# SensorController_revB.net
KiCad netlist of a schematic drawn in EAGLE
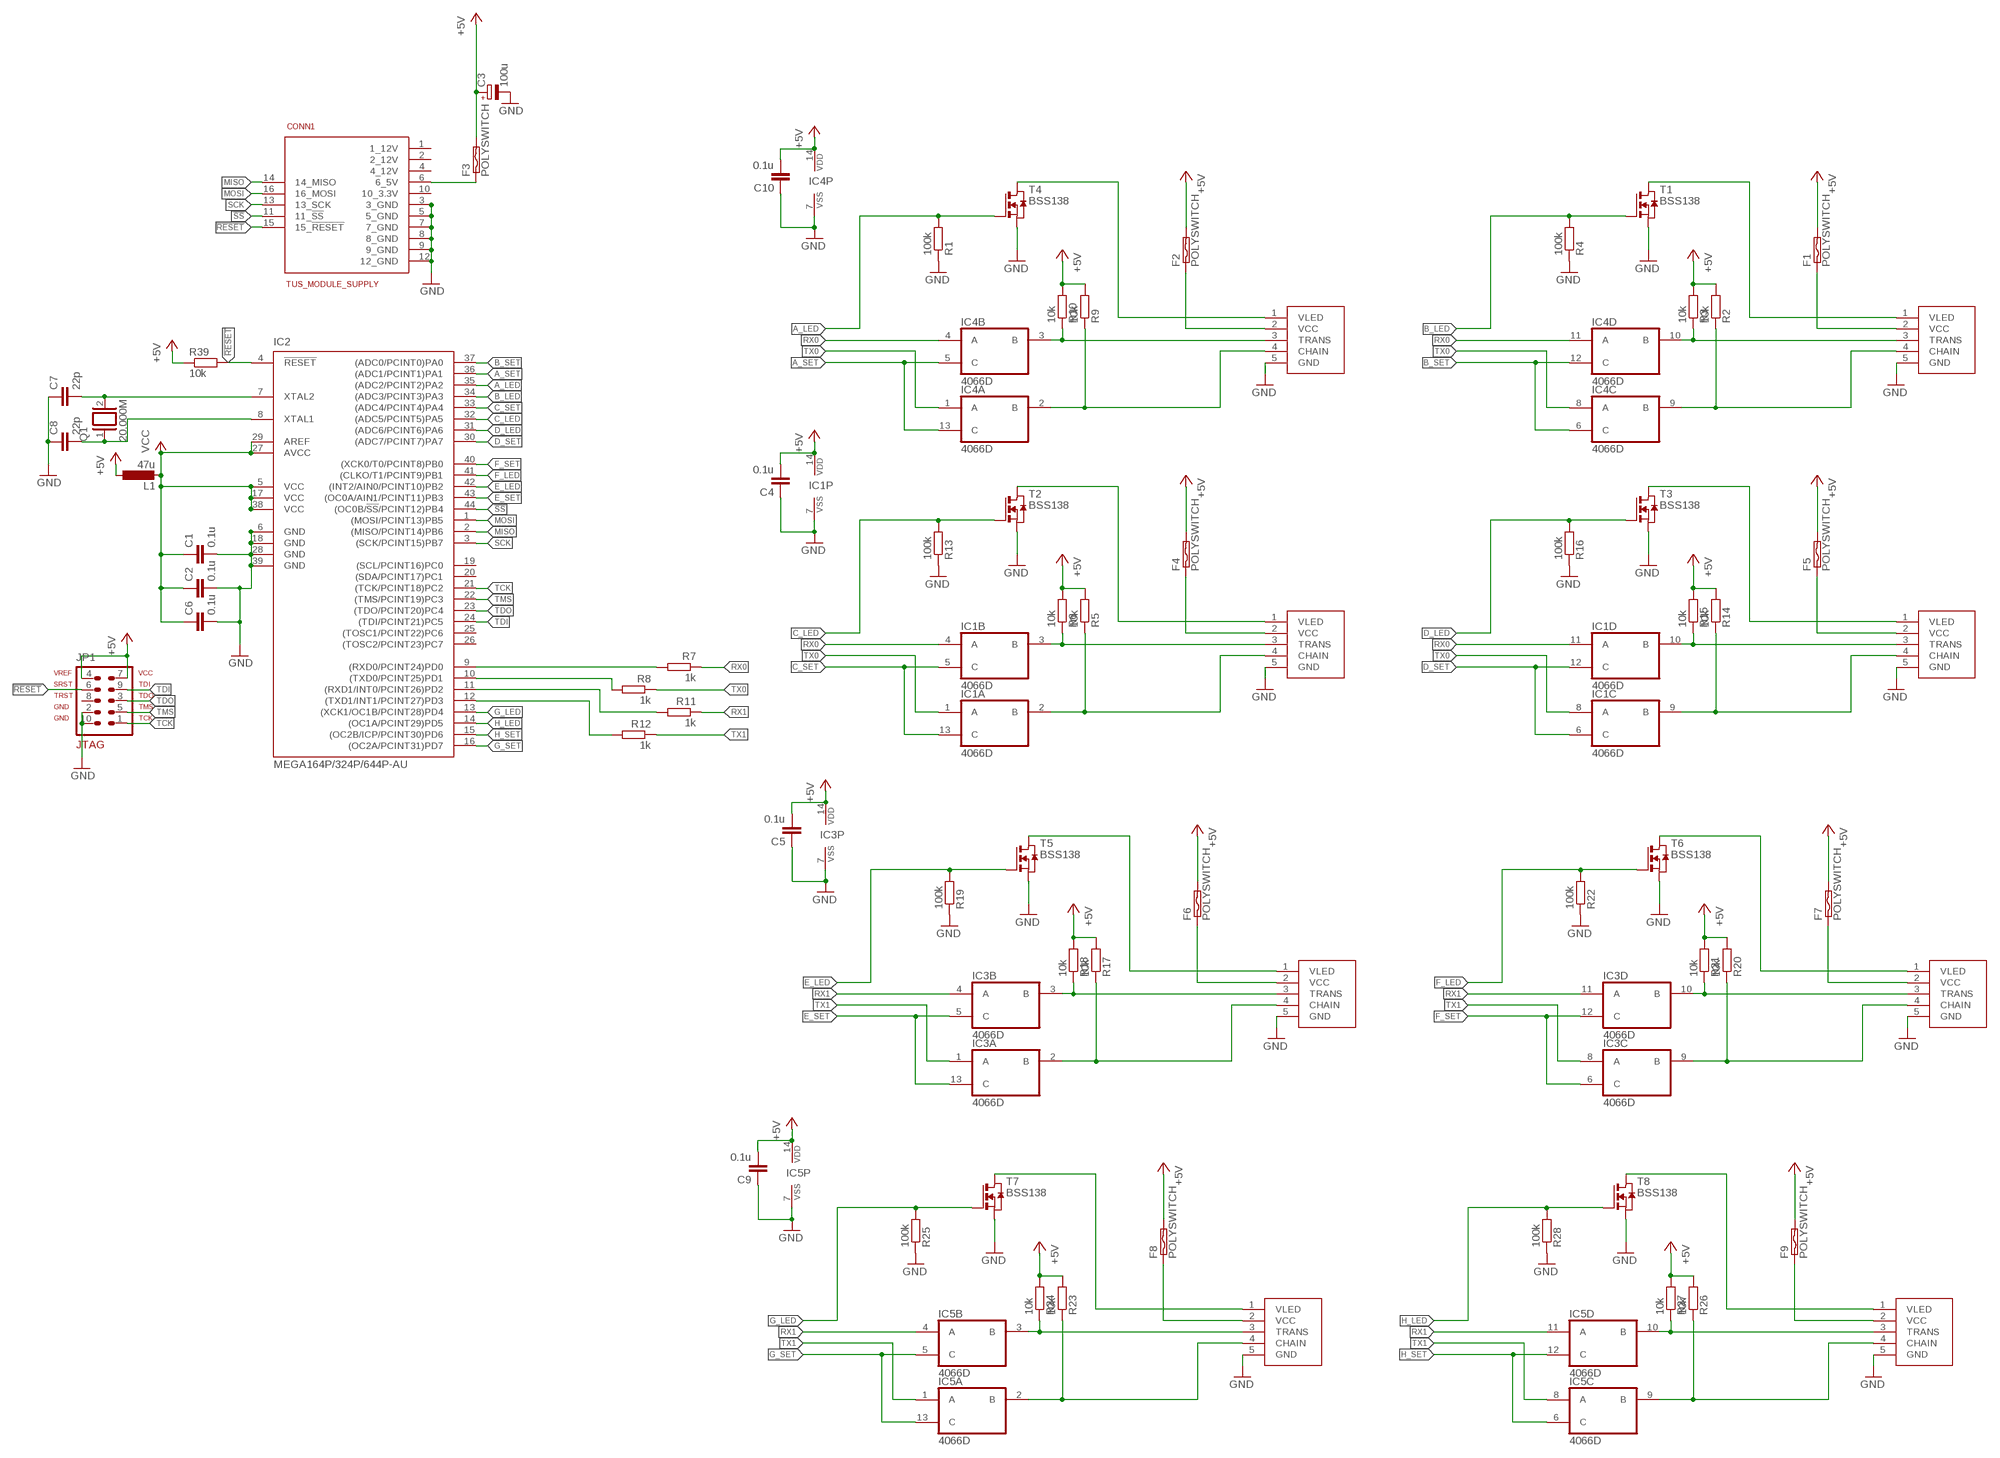
[diagram p0: schematic, sheet 1]

(export (version "E")
  (design (tool "Eeschema 10.0.6"))
  (components
    (comp (ref "A_OUT")
      (value "SERIAL_SENSORXH")
      (footprint "eagle-import:XH-5")
      (libsource (lib "eagle-import") (part "SERIAL_SENSORXH"))
    )
    (comp (ref "B_OUT")
      (value "SERIAL_SENSORXH")
      (footprint "eagle-import:XH-5")
      (libsource (lib "eagle-import") (part "SERIAL_SENSORXH"))
    )
    (comp (ref "C1")
      (value "0.1u")
      (footprint "eagle-import:C1608")
      (libsource (lib "eagle-import") (part "C-EUC1608"))
    )
    (comp (ref "C2")
      (value "0.1u")
      (footprint "eagle-import:C1608")
      (libsource (lib "eagle-import") (part "C-EUC1608"))
    )
    (comp (ref "C3")
      (value "100u")
      (footprint "eagle-import:E2,5-5")
      (libsource (lib "eagle-import") (part "CPOL-EUE2.5-5"))
    )
    (comp (ref "C4")
      (value "0.1u")
      (footprint "eagle-import:C1608")
      (libsource (lib "eagle-import") (part "C-EUC1608"))
    )
    (comp (ref "C5")
      (value "0.1u")
      (footprint "eagle-import:C1608")
      (libsource (lib "eagle-import") (part "C-EUC1608"))
    )
    (comp (ref "C6")
      (value "0.1u")
      (footprint "eagle-import:C1608")
      (libsource (lib "eagle-import") (part "C-EUC1608"))
    )
    (comp (ref "C7")
      (value "22p")
      (footprint "eagle-import:C1608")
      (libsource (lib "eagle-import") (part "C-EUC1608"))
    )
    (comp (ref "C8")
      (value "22p")
      (footprint "eagle-import:C1608")
      (libsource (lib "eagle-import") (part "C-EUC1608"))
    )
    (comp (ref "C9")
      (value "0.1u")
      (footprint "eagle-import:C1608")
      (libsource (lib "eagle-import") (part "C-EUC1608"))
    )
    (comp (ref "C10")
      (value "0.1u")
      (footprint "eagle-import:C1608")
      (libsource (lib "eagle-import") (part "C-EUC1608"))
    )
    (comp (ref "CONN1")
      (value "TUS_MODULE_SUPPLY")
      (footprint "eagle-import:2X08")
      (libsource (lib "eagle-import") (part "TUS_MODULE_SUPPLY"))
    )
    (comp (ref "C_OUT")
      (value "SERIAL_SENSORXH")
      (footprint "eagle-import:XH-5")
      (libsource (lib "eagle-import") (part "SERIAL_SENSORXH"))
    )
    (comp (ref "D_OUT")
      (value "SERIAL_SENSORXH")
      (footprint "eagle-import:XH-5")
      (libsource (lib "eagle-import") (part "SERIAL_SENSORXH"))
    )
    (comp (ref "E_OUT")
      (value "SERIAL_SENSORXH")
      (footprint "eagle-import:XH-5")
      (libsource (lib "eagle-import") (part "SERIAL_SENSORXH"))
    )
    (comp (ref "F1")
      (value "POLYSWITCH")
      (footprint "eagle-import:0207_2V")
      (libsource (lib "eagle-import") (part "POLYSWITCH"))
    )
    (comp (ref "F2")
      (value "POLYSWITCH")
      (footprint "eagle-import:0207_2V")
      (libsource (lib "eagle-import") (part "POLYSWITCH"))
    )
    (comp (ref "F3")
      (value "POLYSWITCH")
      (footprint "eagle-import:0207_2V")
      (libsource (lib "eagle-import") (part "POLYSWITCH"))
    )
    (comp (ref "F4")
      (value "POLYSWITCH")
      (footprint "eagle-import:0207_2V")
      (libsource (lib "eagle-import") (part "POLYSWITCH"))
    )
    (comp (ref "F5")
      (value "POLYSWITCH")
      (footprint "eagle-import:0207_2V")
      (libsource (lib "eagle-import") (part "POLYSWITCH"))
    )
    (comp (ref "F6")
      (value "POLYSWITCH")
      (footprint "eagle-import:0207_2V")
      (libsource (lib "eagle-import") (part "POLYSWITCH"))
    )
    (comp (ref "F7")
      (value "POLYSWITCH")
      (footprint "eagle-import:0207_2V")
      (libsource (lib "eagle-import") (part "POLYSWITCH"))
    )
    (comp (ref "F8")
      (value "POLYSWITCH")
      (footprint "eagle-import:0207_2V")
      (libsource (lib "eagle-import") (part "POLYSWITCH"))
    )
    (comp (ref "F9")
      (value "POLYSWITCH")
      (footprint "eagle-import:0207_2V")
      (libsource (lib "eagle-import") (part "POLYSWITCH"))
    )
    (comp (ref "F_OUT")
      (value "SERIAL_SENSORXH")
      (footprint "eagle-import:XH-5")
      (libsource (lib "eagle-import") (part "SERIAL_SENSORXH"))
    )
    (comp (ref "G_OUT")
      (value "SERIAL_SENSORXH")
      (footprint "eagle-import:XH-5")
      (libsource (lib "eagle-import") (part "SERIAL_SENSORXH"))
    )
    (comp (ref "H_OUT")
      (value "SERIAL_SENSORXH")
      (footprint "eagle-import:XH-5")
      (libsource (lib "eagle-import") (part "SERIAL_SENSORXH"))
    )
    (comp (ref "IC1")
      (value "4066D")
      (footprint "eagle-import:SO14")
      (libsource (lib "eagle-import") (part "4066D"))
    )
    (comp (ref "IC2")
      (value "MEGA164P/324P/644P-AU")
      (footprint "eagle-import:TQFP44")
      (libsource (lib "eagle-import") (part "MEGA164P/324P/644P-AU"))
    )
    (comp (ref "IC3")
      (value "4066D")
      (footprint "eagle-import:SO14")
      (libsource (lib "eagle-import") (part "4066D"))
    )
    (comp (ref "IC4")
      (value "4066D")
      (footprint "eagle-import:SO14")
      (libsource (lib "eagle-import") (part "4066D"))
    )
    (comp (ref "IC5")
      (value "4066D")
      (footprint "eagle-import:SO14")
      (libsource (lib "eagle-import") (part "4066D"))
    )
    (comp (ref "JP1")
      (value "AVR-JTAG-10")
      (footprint "eagle-import:AVR-JTAG-10")
      (libsource (lib "eagle-import") (part "AVR-JTAG-10"))
    )
    (comp (ref "L1")
      (value "47u")
      (footprint "eagle-import:L1812")
      (libsource (lib "eagle-import") (part "L-EUL1812"))
    )
    (comp (ref "Q1")
      (value "20.000M")
      (footprint "eagle-import:QS")
      (libsource (lib "eagle-import") (part "XTAL/S"))
    )
    (comp (ref "R1")
      (value "100k")
      (footprint "eagle-import:R0603")
      (libsource (lib "eagle-import") (part "R-EU_R0603"))
    )
    (comp (ref "R2")
      (value "10k")
      (footprint "eagle-import:R0603")
      (libsource (lib "eagle-import") (part "R-EU_R0603"))
    )
    (comp (ref "R3")
      (value "10k")
      (footprint "eagle-import:R0603")
      (libsource (lib "eagle-import") (part "R-EU_R0603"))
    )
    (comp (ref "R4")
      (value "100k")
      (footprint "eagle-import:R0603")
      (libsource (lib "eagle-import") (part "R-EU_R0603"))
    )
    (comp (ref "R5")
      (value "10k")
      (footprint "eagle-import:R0603")
      (libsource (lib "eagle-import") (part "R-EU_R0603"))
    )
    (comp (ref "R6")
      (value "10k")
      (footprint "eagle-import:R0603")
      (libsource (lib "eagle-import") (part "R-EU_R0603"))
    )
    (comp (ref "R7")
      (value "1k")
      (footprint "eagle-import:R0603")
      (libsource (lib "eagle-import") (part "R-EU_R0603"))
    )
    (comp (ref "R8")
      (value "1k")
      (footprint "eagle-import:R0603")
      (libsource (lib "eagle-import") (part "R-EU_R0603"))
    )
    (comp (ref "R9")
      (value "10k")
      (footprint "eagle-import:R0603")
      (libsource (lib "eagle-import") (part "R-EU_R0603"))
    )
    (comp (ref "R10")
      (value "10k")
      (footprint "eagle-import:R0603")
      (libsource (lib "eagle-import") (part "R-EU_R0603"))
    )
    (comp (ref "R11")
      (value "1k")
      (footprint "eagle-import:R0603")
      (libsource (lib "eagle-import") (part "R-EU_R0603"))
    )
    (comp (ref "R12")
      (value "1k")
      (footprint "eagle-import:R0603")
      (libsource (lib "eagle-import") (part "R-EU_R0603"))
    )
    (comp (ref "R13")
      (value "100k")
      (footprint "eagle-import:R0603")
      (libsource (lib "eagle-import") (part "R-EU_R0603"))
    )
    (comp (ref "R14")
      (value "10k")
      (footprint "eagle-import:R0603")
      (libsource (lib "eagle-import") (part "R-EU_R0603"))
    )
    (comp (ref "R15")
      (value "10k")
      (footprint "eagle-import:R0603")
      (libsource (lib "eagle-import") (part "R-EU_R0603"))
    )
    (comp (ref "R16")
      (value "100k")
      (footprint "eagle-import:R0603")
      (libsource (lib "eagle-import") (part "R-EU_R0603"))
    )
    (comp (ref "R17")
      (value "10k")
      (footprint "eagle-import:R0603")
      (libsource (lib "eagle-import") (part "R-EU_R0603"))
    )
    (comp (ref "R18")
      (value "10k")
      (footprint "eagle-import:R0603")
      (libsource (lib "eagle-import") (part "R-EU_R0603"))
    )
    (comp (ref "R19")
      (value "100k")
      (footprint "eagle-import:R0603")
      (libsource (lib "eagle-import") (part "R-EU_R0603"))
    )
    (comp (ref "R20")
      (value "10k")
      (footprint "eagle-import:R0603")
      (libsource (lib "eagle-import") (part "R-EU_R0603"))
    )
    (comp (ref "R21")
      (value "10k")
      (footprint "eagle-import:R0603")
      (libsource (lib "eagle-import") (part "R-EU_R0603"))
    )
    (comp (ref "R22")
      (value "100k")
      (footprint "eagle-import:R0603")
      (libsource (lib "eagle-import") (part "R-EU_R0603"))
    )
    (comp (ref "R23")
      (value "10k")
      (footprint "eagle-import:R0603")
      (libsource (lib "eagle-import") (part "R-EU_R0603"))
    )
    (comp (ref "R24")
      (value "10k")
      (footprint "eagle-import:R0603")
      (libsource (lib "eagle-import") (part "R-EU_R0603"))
    )
    (comp (ref "R25")
      (value "100k")
      (footprint "eagle-import:R0603")
      (libsource (lib "eagle-import") (part "R-EU_R0603"))
    )
    (comp (ref "R26")
      (value "10k")
      (footprint "eagle-import:R0603")
      (libsource (lib "eagle-import") (part "R-EU_R0603"))
    )
    (comp (ref "R27")
      (value "10k")
      (footprint "eagle-import:R0603")
      (libsource (lib "eagle-import") (part "R-EU_R0603"))
    )
    (comp (ref "R28")
      (value "100k")
      (footprint "eagle-import:R0603")
      (libsource (lib "eagle-import") (part "R-EU_R0603"))
    )
    (comp (ref "R39")
      (value "10k")
      (footprint "eagle-import:R0603")
      (libsource (lib "eagle-import") (part "R-EU_R0603"))
    )
    (comp (ref "T1")
      (value "BSS138")
      (footprint "eagle-import:SOT-23")
      (libsource (lib "eagle-import") (part "NMOSSOT23"))
    )
    (comp (ref "T2")
      (value "BSS138")
      (footprint "eagle-import:SOT-23")
      (libsource (lib "eagle-import") (part "NMOSSOT23"))
    )
    (comp (ref "T3")
      (value "BSS138")
      (footprint "eagle-import:SOT-23")
      (libsource (lib "eagle-import") (part "NMOSSOT23"))
    )
    (comp (ref "T4")
      (value "BSS138")
      (footprint "eagle-import:SOT-23")
      (libsource (lib "eagle-import") (part "NMOSSOT23"))
    )
    (comp (ref "T5")
      (value "BSS138")
      (footprint "eagle-import:SOT-23")
      (libsource (lib "eagle-import") (part "NMOSSOT23"))
    )
    (comp (ref "T6")
      (value "BSS138")
      (footprint "eagle-import:SOT-23")
      (libsource (lib "eagle-import") (part "NMOSSOT23"))
    )
    (comp (ref "T7")
      (value "BSS138")
      (footprint "eagle-import:SOT-23")
      (libsource (lib "eagle-import") (part "NMOSSOT23"))
    )
    (comp (ref "T8")
      (value "BSS138")
      (footprint "eagle-import:SOT-23")
      (libsource (lib "eagle-import") (part "NMOSSOT23"))
    )
  )
  (nets
    (net (code "1") (name "+5V") (class "Default")
      (node (ref "C10") (pin "2") (pinfunction "2_2") (pintype "passive"))
      (node (ref "C3") (pin "+") (pinfunction "+_+") (pintype "passive"))
      (node (ref "C4") (pin "2") (pinfunction "2_2") (pintype "passive"))
      (node (ref "C5") (pin "2") (pinfunction "2_2") (pintype "passive"))
      (node (ref "C9") (pin "2") (pinfunction "2_2") (pintype "passive"))
      (node (ref "F1") (pin "2") (pinfunction "2_2") (pintype "passive"))
      (node (ref "F2") (pin "2") (pinfunction "2_2") (pintype "passive"))
      (node (ref "F3") (pin "2") (pinfunction "2_2") (pintype "passive"))
      (node (ref "F4") (pin "2") (pinfunction "2_2") (pintype "passive"))
      (node (ref "F5") (pin "2") (pinfunction "2_2") (pintype "passive"))
      (node (ref "F6") (pin "2") (pinfunction "2_2") (pintype "passive"))
      (node (ref "F7") (pin "2") (pinfunction "2_2") (pintype "passive"))
      (node (ref "F8") (pin "2") (pinfunction "2_2") (pintype "passive"))
      (node (ref "F9") (pin "2") (pinfunction "2_2") (pintype "passive"))
      (node (ref "IC1") (pin "14") (pinfunction "VDD_14") (pintype "power_in"))
      (node (ref "IC3") (pin "14") (pinfunction "VDD_14") (pintype "power_in"))
      (node (ref "IC4") (pin "14") (pinfunction "VDD_14") (pintype "power_in"))
      (node (ref "IC5") (pin "14") (pinfunction "VDD_14") (pintype "power_in"))
      (node (ref "JP1") (pin "4") (pinfunction "4_4") (pintype "passive"))
      (node (ref "JP1") (pin "7") (pinfunction "7_7") (pintype "passive"))
      (node (ref "L1") (pin "1") (pinfunction "1_1") (pintype "passive"))
      (node (ref "R10") (pin "2") (pinfunction "2_2") (pintype "passive"))
      (node (ref "R14") (pin "2") (pinfunction "2_2") (pintype "passive"))
      (node (ref "R15") (pin "2") (pinfunction "2_2") (pintype "passive"))
      (node (ref "R17") (pin "2") (pinfunction "2_2") (pintype "passive"))
      (node (ref "R18") (pin "2") (pinfunction "2_2") (pintype "passive"))
      (node (ref "R2") (pin "2") (pinfunction "2_2") (pintype "passive"))
      (node (ref "R20") (pin "2") (pinfunction "2_2") (pintype "passive"))
      (node (ref "R21") (pin "2") (pinfunction "2_2") (pintype "passive"))
      (node (ref "R23") (pin "2") (pinfunction "2_2") (pintype "passive"))
      (node (ref "R24") (pin "2") (pinfunction "2_2") (pintype "passive"))
      (node (ref "R26") (pin "2") (pinfunction "2_2") (pintype "passive"))
      (node (ref "R27") (pin "2") (pinfunction "2_2") (pintype "passive"))
      (node (ref "R3") (pin "2") (pinfunction "2_2") (pintype "passive"))
      (node (ref "R39") (pin "1") (pinfunction "1_1") (pintype "passive"))
      (node (ref "R5") (pin "2") (pinfunction "2_2") (pintype "passive"))
      (node (ref "R6") (pin "2") (pinfunction "2_2") (pintype "passive"))
      (node (ref "R9") (pin "2") (pinfunction "2_2") (pintype "passive"))
    )
    (net (code "2") (name "/~{RESET}") (class "Default")
      (node (ref "CONN1") (pin "15") (pinfunction "15_~{RESET}_15") (pintype "bidirectional"))
      (node (ref "IC2") (pin "4") (pinfunction "~{RESET}_4") (pintype "input"))
      (node (ref "JP1") (pin "6") (pinfunction "6_6") (pintype "passive"))
      (node (ref "R39") (pin "2") (pinfunction "2_2") (pintype "passive"))
    )
    (net (code "3") (name "/~{SS}") (class "Default")
      (node (ref "CONN1") (pin "11") (pinfunction "11_~{SS}_11") (pintype "bidirectional"))
      (node (ref "IC2") (pin "44") (pinfunction "(OC0B/~{SS}/PCINT12)PB4_44") (pintype "bidirectional"))
    )
    (net (code "4") (name "A_LED") (class "Default")
      (node (ref "IC2") (pin "35") (pinfunction "(ADC2/PCINT2)PA2_35") (pintype "bidirectional"))
      (node (ref "R1") (pin "2") (pinfunction "2_2") (pintype "passive"))
      (node (ref "T4") (pin "3") (pinfunction "G_3") (pintype "passive"))
    )
    (net (code "5") (name "A_SET") (class "Default")
      (node (ref "IC2") (pin "36") (pinfunction "(ADC1/PCINT1)PA1_36") (pintype "bidirectional"))
      (node (ref "IC4") (pin "13") (pinfunction "C_13") (pintype "input"))
      (node (ref "IC4") (pin "5") (pinfunction "C_5") (pintype "input"))
    )
    (net (code "6") (name "B_LED") (class "Default")
      (node (ref "IC2") (pin "34") (pinfunction "(ADC3/PCINT3)PA3_34") (pintype "bidirectional"))
      (node (ref "R4") (pin "2") (pinfunction "2_2") (pintype "passive"))
      (node (ref "T1") (pin "3") (pinfunction "G_3") (pintype "passive"))
    )
    (net (code "7") (name "B_SET") (class "Default")
      (node (ref "IC2") (pin "37") (pinfunction "(ADC0/PCINT0)PA0_37") (pintype "bidirectional"))
      (node (ref "IC4") (pin "12") (pinfunction "C_12") (pintype "input"))
      (node (ref "IC4") (pin "6") (pinfunction "C_6") (pintype "input"))
    )
    (net (code "8") (name "C_LED") (class "Default")
      (node (ref "IC2") (pin "32") (pinfunction "(ADC5/PCINT5)PA5_32") (pintype "bidirectional"))
      (node (ref "R13") (pin "2") (pinfunction "2_2") (pintype "passive"))
      (node (ref "T2") (pin "3") (pinfunction "G_3") (pintype "passive"))
    )
    (net (code "9") (name "C_SET") (class "Default")
      (node (ref "IC1") (pin "13") (pinfunction "C_13") (pintype "input"))
      (node (ref "IC1") (pin "5") (pinfunction "C_5") (pintype "input"))
      (node (ref "IC2") (pin "33") (pinfunction "(ADC4/PCINT4)PA4_33") (pintype "bidirectional"))
    )
    (net (code "10") (name "D_LED") (class "Default")
      (node (ref "IC2") (pin "31") (pinfunction "(ADC6/PCINT6)PA6_31") (pintype "bidirectional"))
      (node (ref "R16") (pin "2") (pinfunction "2_2") (pintype "passive"))
      (node (ref "T3") (pin "3") (pinfunction "G_3") (pintype "passive"))
    )
    (net (code "11") (name "D_SET") (class "Default")
      (node (ref "IC1") (pin "12") (pinfunction "C_12") (pintype "input"))
      (node (ref "IC1") (pin "6") (pinfunction "C_6") (pintype "input"))
      (node (ref "IC2") (pin "30") (pinfunction "(ADC7/PCINT7)PA7_30") (pintype "bidirectional"))
    )
    (net (code "12") (name "E_LED") (class "Default")
      (node (ref "IC2") (pin "42") (pinfunction "(INT2/AIN0/PCINT10)PB2_42") (pintype "bidirectional"))
      (node (ref "R19") (pin "2") (pinfunction "2_2") (pintype "passive"))
      (node (ref "T5") (pin "3") (pinfunction "G_3") (pintype "passive"))
    )
    (net (code "13") (name "E_SET") (class "Default")
      (node (ref "IC2") (pin "43") (pinfunction "(OC0A/AIN1/PCINT11)PB3_43") (pintype "bidirectional"))
      (node (ref "IC3") (pin "13") (pinfunction "C_13") (pintype "input"))
      (node (ref "IC3") (pin "5") (pinfunction "C_5") (pintype "input"))
    )
    (net (code "14") (name "F_LED") (class "Default")
      (node (ref "IC2") (pin "41") (pinfunction "(CLKO/T1/PCINT9)PB1_41") (pintype "bidirectional"))
      (node (ref "R22") (pin "2") (pinfunction "2_2") (pintype "passive"))
      (node (ref "T6") (pin "3") (pinfunction "G_3") (pintype "passive"))
    )
    (net (code "15") (name "F_SET") (class "Default")
      (node (ref "IC2") (pin "40") (pinfunction "(XCK0/T0/PCINT8)PB0_40") (pintype "bidirectional"))
      (node (ref "IC3") (pin "12") (pinfunction "C_12") (pintype "input"))
      (node (ref "IC3") (pin "6") (pinfunction "C_6") (pintype "input"))
    )
    (net (code "16") (name "GND") (class "Default")
      (node (ref "A_OUT") (pin "5") (pinfunction "GND_5") (pintype "bidirectional"))
      (node (ref "B_OUT") (pin "5") (pinfunction "GND_5") (pintype "bidirectional"))
      (node (ref "C1") (pin "2") (pinfunction "2_2") (pintype "passive"))
      (node (ref "C10") (pin "1") (pinfunction "1_1") (pintype "passive"))
      (node (ref "C2") (pin "2") (pinfunction "2_2") (pintype "passive"))
      (node (ref "C3") (pin "-") (pinfunction "-_-") (pintype "passive"))
      (node (ref "C4") (pin "1") (pinfunction "1_1") (pintype "passive"))
      (node (ref "C5") (pin "1") (pinfunction "1_1") (pintype "passive"))
      (node (ref "C6") (pin "2") (pinfunction "2_2") (pintype "passive"))
      (node (ref "C7") (pin "1") (pinfunction "1_1") (pintype "passive"))
      (node (ref "C8") (pin "1") (pinfunction "1_1") (pintype "passive"))
      (node (ref "C9") (pin "1") (pinfunction "1_1") (pintype "passive"))
      (node (ref "CONN1") (pin "12") (pinfunction "12_GND_12") (pintype "bidirectional"))
      (node (ref "CONN1") (pin "3") (pinfunction "3_GND_3") (pintype "bidirectional"))
      (node (ref "CONN1") (pin "5") (pinfunction "5_GND_5") (pintype "bidirectional"))
      (node (ref "CONN1") (pin "7") (pinfunction "7_GND_7") (pintype "bidirectional"))
      (node (ref "CONN1") (pin "8") (pinfunction "8_GND_8") (pintype "bidirectional"))
      (node (ref "CONN1") (pin "9") (pinfunction "9_GND_9") (pintype "bidirectional"))
      (node (ref "C_OUT") (pin "5") (pinfunction "GND_5") (pintype "bidirectional"))
      (node (ref "D_OUT") (pin "5") (pinfunction "GND_5") (pintype "bidirectional"))
      (node (ref "E_OUT") (pin "5") (pinfunction "GND_5") (pintype "bidirectional"))
      (node (ref "F_OUT") (pin "5") (pinfunction "GND_5") (pintype "bidirectional"))
      (node (ref "G_OUT") (pin "5") (pinfunction "GND_5") (pintype "bidirectional"))
      (node (ref "H_OUT") (pin "5") (pinfunction "GND_5") (pintype "bidirectional"))
      (node (ref "IC1") (pin "7") (pinfunction "VSS_7") (pintype "power_in"))
      (node (ref "IC2") (pin "18") (pinfunction "GND_18") (pintype "power_in"))
      (node (ref "IC2") (pin "28") (pinfunction "GND_28") (pintype "power_in"))
      (node (ref "IC2") (pin "39") (pinfunction "GND_39") (pintype "power_in"))
      (node (ref "IC2") (pin "6") (pinfunction "GND_6") (pintype "power_in"))
      (node (ref "IC3") (pin "7") (pinfunction "VSS_7") (pintype "power_in"))
      (node (ref "IC4") (pin "7") (pinfunction "VSS_7") (pintype "power_in"))
      (node (ref "IC5") (pin "7") (pinfunction "VSS_7") (pintype "power_in"))
      (node (ref "JP1") (pin "10") (pinfunction "10_10") (pintype "passive"))
      (node (ref "JP1") (pin "2") (pinfunction "2_2") (pintype "passive"))
      (node (ref "R1") (pin "1") (pinfunction "1_1") (pintype "passive"))
      (node (ref "R13") (pin "1") (pinfunction "1_1") (pintype "passive"))
      (node (ref "R16") (pin "1") (pinfunction "1_1") (pintype "passive"))
      (node (ref "R19") (pin "1") (pinfunction "1_1") (pintype "passive"))
      (node (ref "R22") (pin "1") (pinfunction "1_1") (pintype "passive"))
      (node (ref "R25") (pin "1") (pinfunction "1_1") (pintype "passive"))
      (node (ref "R28") (pin "1") (pinfunction "1_1") (pintype "passive"))
      (node (ref "R4") (pin "1") (pinfunction "1_1") (pintype "passive"))
      (node (ref "T1") (pin "2") (pinfunction "S_2") (pintype "passive"))
      (node (ref "T2") (pin "2") (pinfunction "S_2") (pintype "passive"))
      (node (ref "T3") (pin "2") (pinfunction "S_2") (pintype "passive"))
      (node (ref "T4") (pin "2") (pinfunction "S_2") (pintype "passive"))
      (node (ref "T5") (pin "2") (pinfunction "S_2") (pintype "passive"))
      (node (ref "T6") (pin "2") (pinfunction "S_2") (pintype "passive"))
      (node (ref "T7") (pin "2") (pinfunction "S_2") (pintype "passive"))
      (node (ref "T8") (pin "2") (pinfunction "S_2") (pintype "passive"))
    )
    (net (code "17") (name "G_LED") (class "Default")
      (node (ref "IC2") (pin "13") (pinfunction "(XCK1/OC1B/PCINT28)PD4_13") (pintype "bidirectional"))
      (node (ref "R25") (pin "2") (pinfunction "2_2") (pintype "passive"))
      (node (ref "T7") (pin "3") (pinfunction "G_3") (pintype "passive"))
    )
    (net (code "18") (name "G_SET") (class "Default")
      (node (ref "IC2") (pin "16") (pinfunction "(OC2A/PCINT31)PD7_16") (pintype "bidirectional"))
      (node (ref "IC5") (pin "13") (pinfunction "C_13") (pintype "input"))
      (node (ref "IC5") (pin "5") (pinfunction "C_5") (pintype "input"))
    )
    (net (code "19") (name "H_LED") (class "Default")
      (node (ref "IC2") (pin "14") (pinfunction "(OC1A/PCINT29)PD5_14") (pintype "bidirectional"))
      (node (ref "R28") (pin "2") (pinfunction "2_2") (pintype "passive"))
      (node (ref "T8") (pin "3") (pinfunction "G_3") (pintype "passive"))
    )
    (net (code "20") (name "H_SET") (class "Default")
      (node (ref "IC2") (pin "15") (pinfunction "(OC2B/ICP/PCINT30)PD6_15") (pintype "bidirectional"))
      (node (ref "IC5") (pin "12") (pinfunction "C_12") (pintype "input"))
      (node (ref "IC5") (pin "6") (pinfunction "C_6") (pintype "input"))
    )
    (net (code "21") (name "MISO") (class "Default")
      (node (ref "CONN1") (pin "14") (pinfunction "14_MISO_14") (pintype "bidirectional"))
      (node (ref "IC2") (pin "2") (pinfunction "(MISO/PCINT14)PB6_2") (pintype "bidirectional"))
    )
    (net (code "22") (name "MOSI") (class "Default")
      (node (ref "CONN1") (pin "16") (pinfunction "16_MOSI_16") (pintype "bidirectional"))
      (node (ref "IC2") (pin "1") (pinfunction "(MOSI/PCINT13)PB5_1") (pintype "bidirectional"))
    )
    (net (code "23") (name "Net-(A_OUT-CHAIN)") (class "Default")
      (node (ref "A_OUT") (pin "4") (pinfunction "CHAIN_4") (pintype "bidirectional"))
      (node (ref "IC4") (pin "2") (pinfunction "B_2") (pintype "tri_state"))
      (node (ref "R9") (pin "1") (pinfunction "1_1") (pintype "passive"))
    )
    (net (code "24") (name "Net-(A_OUT-TRANS)") (class "Default")
      (node (ref "A_OUT") (pin "3") (pinfunction "TRANS_3") (pintype "bidirectional"))
      (node (ref "IC4") (pin "3") (pinfunction "B_3") (pintype "tri_state"))
      (node (ref "R10") (pin "1") (pinfunction "1_1") (pintype "passive"))
    )
    (net (code "25") (name "Net-(A_OUT-VCC)") (class "Default")
      (node (ref "A_OUT") (pin "2") (pinfunction "VCC_2") (pintype "bidirectional"))
      (node (ref "F2") (pin "1") (pinfunction "1_1") (pintype "passive"))
    )
    (net (code "26") (name "Net-(A_OUT-VLED)") (class "Default")
      (node (ref "A_OUT") (pin "1") (pinfunction "VLED_1") (pintype "bidirectional"))
      (node (ref "T4") (pin "1") (pinfunction "D_1") (pintype "passive"))
    )
    (net (code "27") (name "Net-(B_OUT-CHAIN)") (class "Default")
      (node (ref "B_OUT") (pin "4") (pinfunction "CHAIN_4") (pintype "bidirectional"))
      (node (ref "IC4") (pin "9") (pinfunction "B_9") (pintype "tri_state"))
      (node (ref "R2") (pin "1") (pinfunction "1_1") (pintype "passive"))
    )
    (net (code "28") (name "Net-(B_OUT-TRANS)") (class "Default")
      (node (ref "B_OUT") (pin "3") (pinfunction "TRANS_3") (pintype "bidirectional"))
      (node (ref "IC4") (pin "10") (pinfunction "B_10") (pintype "tri_state"))
      (node (ref "R3") (pin "1") (pinfunction "1_1") (pintype "passive"))
    )
    (net (code "29") (name "Net-(B_OUT-VCC)") (class "Default")
      (node (ref "B_OUT") (pin "2") (pinfunction "VCC_2") (pintype "bidirectional"))
      (node (ref "F1") (pin "1") (pinfunction "1_1") (pintype "passive"))
    )
    (net (code "30") (name "Net-(B_OUT-VLED)") (class "Default")
      (node (ref "B_OUT") (pin "1") (pinfunction "VLED_1") (pintype "bidirectional"))
      (node (ref "T1") (pin "1") (pinfunction "D_1") (pintype "passive"))
    )
    (net (code "31") (name "Net-(CONN1-6_5V)") (class "Default")
      (node (ref "CONN1") (pin "6") (pinfunction "6_5V_6") (pintype "bidirectional"))
      (node (ref "F3") (pin "1") (pinfunction "1_1") (pintype "passive"))
    )
    (net (code "32") (name "Net-(C_OUT-CHAIN)") (class "Default")
      (node (ref "C_OUT") (pin "4") (pinfunction "CHAIN_4") (pintype "bidirectional"))
      (node (ref "IC1") (pin "2") (pinfunction "B_2") (pintype "tri_state"))
      (node (ref "R5") (pin "1") (pinfunction "1_1") (pintype "passive"))
    )
    (net (code "33") (name "Net-(C_OUT-TRANS)") (class "Default")
      (node (ref "C_OUT") (pin "3") (pinfunction "TRANS_3") (pintype "bidirectional"))
      (node (ref "IC1") (pin "3") (pinfunction "B_3") (pintype "tri_state"))
      (node (ref "R6") (pin "1") (pinfunction "1_1") (pintype "passive"))
    )
    (net (code "34") (name "Net-(C_OUT-VCC)") (class "Default")
      (node (ref "C_OUT") (pin "2") (pinfunction "VCC_2") (pintype "bidirectional"))
      (node (ref "F4") (pin "1") (pinfunction "1_1") (pintype "passive"))
    )
    (net (code "35") (name "Net-(C_OUT-VLED)") (class "Default")
      (node (ref "C_OUT") (pin "1") (pinfunction "VLED_1") (pintype "bidirectional"))
      (node (ref "T2") (pin "1") (pinfunction "D_1") (pintype "passive"))
    )
    (net (code "36") (name "Net-(D_OUT-CHAIN)") (class "Default")
      (node (ref "D_OUT") (pin "4") (pinfunction "CHAIN_4") (pintype "bidirectional"))
      (node (ref "IC1") (pin "9") (pinfunction "B_9") (pintype "tri_state"))
      (node (ref "R14") (pin "1") (pinfunction "1_1") (pintype "passive"))
    )
    (net (code "37") (name "Net-(D_OUT-TRANS)") (class "Default")
      (node (ref "D_OUT") (pin "3") (pinfunction "TRANS_3") (pintype "bidirectional"))
      (node (ref "IC1") (pin "10") (pinfunction "B_10") (pintype "tri_state"))
      (node (ref "R15") (pin "1") (pinfunction "1_1") (pintype "passive"))
    )
    (net (code "38") (name "Net-(D_OUT-VCC)") (class "Default")
      (node (ref "D_OUT") (pin "2") (pinfunction "VCC_2") (pintype "bidirectional"))
      (node (ref "F5") (pin "1") (pinfunction "1_1") (pintype "passive"))
    )
    (net (code "39") (name "Net-(D_OUT-VLED)") (class "Default")
      (node (ref "D_OUT") (pin "1") (pinfunction "VLED_1") (pintype "bidirectional"))
      (node (ref "T3") (pin "1") (pinfunction "D_1") (pintype "passive"))
    )
    (net (code "40") (name "Net-(E_OUT-CHAIN)") (class "Default")
      (node (ref "E_OUT") (pin "4") (pinfunction "CHAIN_4") (pintype "bidirectional"))
      (node (ref "IC3") (pin "2") (pinfunction "B_2") (pintype "tri_state"))
      (node (ref "R17") (pin "1") (pinfunction "1_1") (pintype "passive"))
    )
    (net (code "41") (name "Net-(E_OUT-TRANS)") (class "Default")
      (node (ref "E_OUT") (pin "3") (pinfunction "TRANS_3") (pintype "bidirectional"))
      (node (ref "IC3") (pin "3") (pinfunction "B_3") (pintype "tri_state"))
      (node (ref "R18") (pin "1") (pinfunction "1_1") (pintype "passive"))
    )
    (net (code "42") (name "Net-(E_OUT-VCC)") (class "Default")
      (node (ref "E_OUT") (pin "2") (pinfunction "VCC_2") (pintype "bidirectional"))
      (node (ref "F6") (pin "1") (pinfunction "1_1") (pintype "passive"))
    )
    (net (code "43") (name "Net-(E_OUT-VLED)") (class "Default")
      (node (ref "E_OUT") (pin "1") (pinfunction "VLED_1") (pintype "bidirectional"))
      (node (ref "T5") (pin "1") (pinfunction "D_1") (pintype "passive"))
    )
    (net (code "44") (name "Net-(F_OUT-CHAIN)") (class "Default")
      (node (ref "F_OUT") (pin "4") (pinfunction "CHAIN_4") (pintype "bidirectional"))
      (node (ref "IC3") (pin "9") (pinfunction "B_9") (pintype "tri_state"))
      (node (ref "R20") (pin "1") (pinfunction "1_1") (pintype "passive"))
    )
    (net (code "45") (name "Net-(F_OUT-TRANS)") (class "Default")
      (node (ref "F_OUT") (pin "3") (pinfunction "TRANS_3") (pintype "bidirectional"))
      (node (ref "IC3") (pin "10") (pinfunction "B_10") (pintype "tri_state"))
      (node (ref "R21") (pin "1") (pinfunction "1_1") (pintype "passive"))
    )
    (net (code "46") (name "Net-(F_OUT-VCC)") (class "Default")
      (node (ref "F7") (pin "1") (pinfunction "1_1") (pintype "passive"))
      (node (ref "F_OUT") (pin "2") (pinfunction "VCC_2") (pintype "bidirectional"))
    )
    (net (code "47") (name "Net-(F_OUT-VLED)") (class "Default")
      (node (ref "F_OUT") (pin "1") (pinfunction "VLED_1") (pintype "bidirectional"))
      (node (ref "T6") (pin "1") (pinfunction "D_1") (pintype "passive"))
    )
    (net (code "48") (name "Net-(G_OUT-CHAIN)") (class "Default")
      (node (ref "G_OUT") (pin "4") (pinfunction "CHAIN_4") (pintype "bidirectional"))
      (node (ref "IC5") (pin "2") (pinfunction "B_2") (pintype "tri_state"))
      (node (ref "R23") (pin "1") (pinfunction "1_1") (pintype "passive"))
    )
    (net (code "49") (name "Net-(G_OUT-TRANS)") (class "Default")
      (node (ref "G_OUT") (pin "3") (pinfunction "TRANS_3") (pintype "bidirectional"))
      (node (ref "IC5") (pin "3") (pinfunction "B_3") (pintype "tri_state"))
      (node (ref "R24") (pin "1") (pinfunction "1_1") (pintype "passive"))
    )
    (net (code "50") (name "Net-(G_OUT-VCC)") (class "Default")
      (node (ref "F8") (pin "1") (pinfunction "1_1") (pintype "passive"))
      (node (ref "G_OUT") (pin "2") (pinfunction "VCC_2") (pintype "bidirectional"))
    )
    (net (code "51") (name "Net-(G_OUT-VLED)") (class "Default")
      (node (ref "G_OUT") (pin "1") (pinfunction "VLED_1") (pintype "bidirectional"))
      (node (ref "T7") (pin "1") (pinfunction "D_1") (pintype "passive"))
    )
    (net (code "52") (name "Net-(H_OUT-CHAIN)") (class "Default")
      (node (ref "H_OUT") (pin "4") (pinfunction "CHAIN_4") (pintype "bidirectional"))
      (node (ref "IC5") (pin "9") (pinfunction "B_9") (pintype "tri_state"))
      (node (ref "R26") (pin "1") (pinfunction "1_1") (pintype "passive"))
    )
    (net (code "53") (name "Net-(H_OUT-TRANS)") (class "Default")
      (node (ref "H_OUT") (pin "3") (pinfunction "TRANS_3") (pintype "bidirectional"))
      (node (ref "IC5") (pin "10") (pinfunction "B_10") (pintype "tri_state"))
      (node (ref "R27") (pin "1") (pinfunction "1_1") (pintype "passive"))
    )
    (net (code "54") (name "Net-(H_OUT-VCC)") (class "Default")
      (node (ref "F9") (pin "1") (pinfunction "1_1") (pintype "passive"))
      (node (ref "H_OUT") (pin "2") (pinfunction "VCC_2") (pintype "bidirectional"))
    )
    (net (code "55") (name "Net-(H_OUT-VLED)") (class "Default")
      (node (ref "H_OUT") (pin "1") (pinfunction "VLED_1") (pintype "bidirectional"))
      (node (ref "T8") (pin "1") (pinfunction "D_1") (pintype "passive"))
    )
    (net (code "56") (name "Net-(IC2-(RXD0{slash}PCINT24)PD0)") (class "Default")
      (node (ref "IC2") (pin "9") (pinfunction "(RXD0/PCINT24)PD0_9") (pintype "bidirectional"))
      (node (ref "R7") (pin "2") (pinfunction "2_2") (pintype "passive"))
    )
    (net (code "57") (name "Net-(IC2-(RXD1{slash}INT0{slash}PCINT26)PD2)") (class "Default")
      (node (ref "IC2") (pin "11") (pinfunction "(RXD1/INT0/PCINT26)PD2_11") (pintype "bidirectional"))
      (node (ref "R11") (pin "2") (pinfunction "2_2") (pintype "passive"))
    )
    (net (code "58") (name "Net-(IC2-(TXD0{slash}PCINT25)PD1)") (class "Default")
      (node (ref "IC2") (pin "10") (pinfunction "(TXD0/PCINT25)PD1_10") (pintype "bidirectional"))
      (node (ref "R8") (pin "2") (pinfunction "2_2") (pintype "passive"))
    )
    (net (code "59") (name "Net-(IC2-(TXD1{slash}INT1{slash}PCINT27)PD3)") (class "Default")
      (node (ref "IC2") (pin "12") (pinfunction "(TXD1/INT1/PCINT27)PD3_12") (pintype "bidirectional"))
      (node (ref "R12") (pin "2") (pinfunction "2_2") (pintype "passive"))
    )
    (net (code "60") (name "Net-(IC2-XTAL1)") (class "Default")
      (node (ref "C8") (pin "2") (pinfunction "2_2") (pintype "passive"))
      (node (ref "IC2") (pin "8") (pinfunction "XTAL1_8") (pintype "input"))
      (node (ref "Q1") (pin "1") (pinfunction "1_1") (pintype "passive"))
    )
    (net (code "61") (name "Net-(IC2-XTAL2)") (class "Default")
      (node (ref "C7") (pin "2") (pinfunction "2_2") (pintype "passive"))
      (node (ref "IC2") (pin "7") (pinfunction "XTAL2_7") (pintype "output"))
      (node (ref "Q1") (pin "2") (pinfunction "2_2") (pintype "passive"))
    )
    (net (code "62") (name "RX0") (class "Default")
      (node (ref "IC1") (pin "11") (pinfunction "A_11") (pintype "tri_state"))
      (node (ref "IC1") (pin "4") (pinfunction "A_4") (pintype "tri_state"))
      (node (ref "IC4") (pin "11") (pinfunction "A_11") (pintype "tri_state"))
      (node (ref "IC4") (pin "4") (pinfunction "A_4") (pintype "tri_state"))
      (node (ref "R7") (pin "1") (pinfunction "1_1") (pintype "passive"))
    )
    (net (code "63") (name "RX1") (class "Default")
      (node (ref "IC3") (pin "11") (pinfunction "A_11") (pintype "tri_state"))
      (node (ref "IC3") (pin "4") (pinfunction "A_4") (pintype "tri_state"))
      (node (ref "IC5") (pin "11") (pinfunction "A_11") (pintype "tri_state"))
      (node (ref "IC5") (pin "4") (pinfunction "A_4") (pintype "tri_state"))
      (node (ref "R11") (pin "1") (pinfunction "1_1") (pintype "passive"))
    )
    (net (code "64") (name "SCK") (class "Default")
      (node (ref "CONN1") (pin "13") (pinfunction "13_SCK_13") (pintype "bidirectional"))
      (node (ref "IC2") (pin "3") (pinfunction "(SCK/PCINT15)PB7_3") (pintype "bidirectional"))
    )
    (net (code "65") (name "TCK") (class "Default")
      (node (ref "IC2") (pin "21") (pinfunction "(TCK/PCINT18)PC2_21") (pintype "bidirectional"))
      (node (ref "JP1") (pin "1") (pinfunction "1_1") (pintype "passive"))
    )
    (net (code "66") (name "TDI") (class "Default")
      (node (ref "IC2") (pin "24") (pinfunction "(TDI/PCINT21)PC5_24") (pintype "bidirectional"))
      (node (ref "JP1") (pin "9") (pinfunction "9_9") (pintype "passive"))
    )
    (net (code "67") (name "TDO") (class "Default")
      (node (ref "IC2") (pin "23") (pinfunction "(TDO/PCINT20)PC4_23") (pintype "bidirectional"))
      (node (ref "JP1") (pin "3") (pinfunction "3_3") (pintype "passive"))
    )
    (net (code "68") (name "TMS") (class "Default")
      (node (ref "IC2") (pin "22") (pinfunction "(TMS/PCINT19)PC3_22") (pintype "bidirectional"))
      (node (ref "JP1") (pin "5") (pinfunction "5_5") (pintype "passive"))
    )
    (net (code "69") (name "TX0") (class "Default")
      (node (ref "IC1") (pin "1") (pinfunction "A_1") (pintype "tri_state"))
      (node (ref "IC1") (pin "8") (pinfunction "A_8") (pintype "tri_state"))
      (node (ref "IC4") (pin "1") (pinfunction "A_1") (pintype "tri_state"))
      (node (ref "IC4") (pin "8") (pinfunction "A_8") (pintype "tri_state"))
      (node (ref "R8") (pin "1") (pinfunction "1_1") (pintype "passive"))
    )
    (net (code "70") (name "TX1") (class "Default")
      (node (ref "IC3") (pin "1") (pinfunction "A_1") (pintype "tri_state"))
      (node (ref "IC3") (pin "8") (pinfunction "A_8") (pintype "tri_state"))
      (node (ref "IC5") (pin "1") (pinfunction "A_1") (pintype "tri_state"))
      (node (ref "IC5") (pin "8") (pinfunction "A_8") (pintype "tri_state"))
      (node (ref "R12") (pin "1") (pinfunction "1_1") (pintype "passive"))
    )
    (net (code "71") (name "VCC") (class "Default")
      (node (ref "C1") (pin "1") (pinfunction "1_1") (pintype "passive"))
      (node (ref "C2") (pin "1") (pinfunction "1_1") (pintype "passive"))
      (node (ref "C6") (pin "1") (pinfunction "1_1") (pintype "passive"))
      (node (ref "IC2") (pin "17") (pinfunction "VCC_17") (pintype "power_in"))
      (node (ref "IC2") (pin "27") (pinfunction "AVCC_27") (pintype "power_in"))
      (node (ref "IC2") (pin "29") (pinfunction "AREF_29") (pintype "power_in"))
      (node (ref "IC2") (pin "38") (pinfunction "VCC_38") (pintype "power_in"))
      (node (ref "IC2") (pin "5") (pinfunction "VCC_5") (pintype "power_in"))
      (node (ref "L1") (pin "2") (pinfunction "2_2") (pintype "passive"))
    )
    (net (code "72") (name "unconnected-(CONN1-1_12V-Pad1)") (class "Default")
      (node (ref "CONN1") (pin "1") (pinfunction "1_12V_1") (pintype "bidirectional"))
    )
    (net (code "73") (name "unconnected-(CONN1-2_12V-Pad2)") (class "Default")
      (node (ref "CONN1") (pin "2") (pinfunction "2_12V_2") (pintype "bidirectional"))
    )
    (net (code "74") (name "unconnected-(CONN1-4_12V-Pad4)") (class "Default")
      (node (ref "CONN1") (pin "4") (pinfunction "4_12V_4") (pintype "bidirectional"))
    )
    (net (code "75") (name "unconnected-(CONN1-10_3.3V-Pad10)") (class "Default")
      (node (ref "CONN1") (pin "10") (pinfunction "10_3.3V_10") (pintype "bidirectional"))
    )
    (net (code "76") (name "unconnected-(IC2-(SCL{slash}PCINT16)PC0-Pad19)") (class "Default")
      (node (ref "IC2") (pin "19") (pinfunction "(SCL/PCINT16)PC0_19") (pintype "bidirectional"))
    )
    (net (code "77") (name "unconnected-(IC2-(SDA{slash}PCINT17)PC1-Pad20)") (class "Default")
      (node (ref "IC2") (pin "20") (pinfunction "(SDA/PCINT17)PC1_20") (pintype "bidirectional"))
    )
    (net (code "78") (name "unconnected-(IC2-(TOSC1{slash}PCINT22)PC6-Pad25)") (class "Default")
      (node (ref "IC2") (pin "25") (pinfunction "(TOSC1/PCINT22)PC6_25") (pintype "bidirectional"))
    )
    (net (code "79") (name "unconnected-(IC2-(TOSC2{slash}PCINT23)PC7-Pad26)") (class "Default")
      (node (ref "IC2") (pin "26") (pinfunction "(TOSC2/PCINT23)PC7_26") (pintype "bidirectional"))
    )
    (net (code "80") (name "unconnected-(JP1-Pad8)") (class "Default")
      (node (ref "JP1") (pin "8") (pinfunction "8_8") (pintype "passive"))
    )
  )
)
